# SCH_rfid2final_2025-07-08_1.net
KiCad netlist of a schematic drawn in EasyEDA
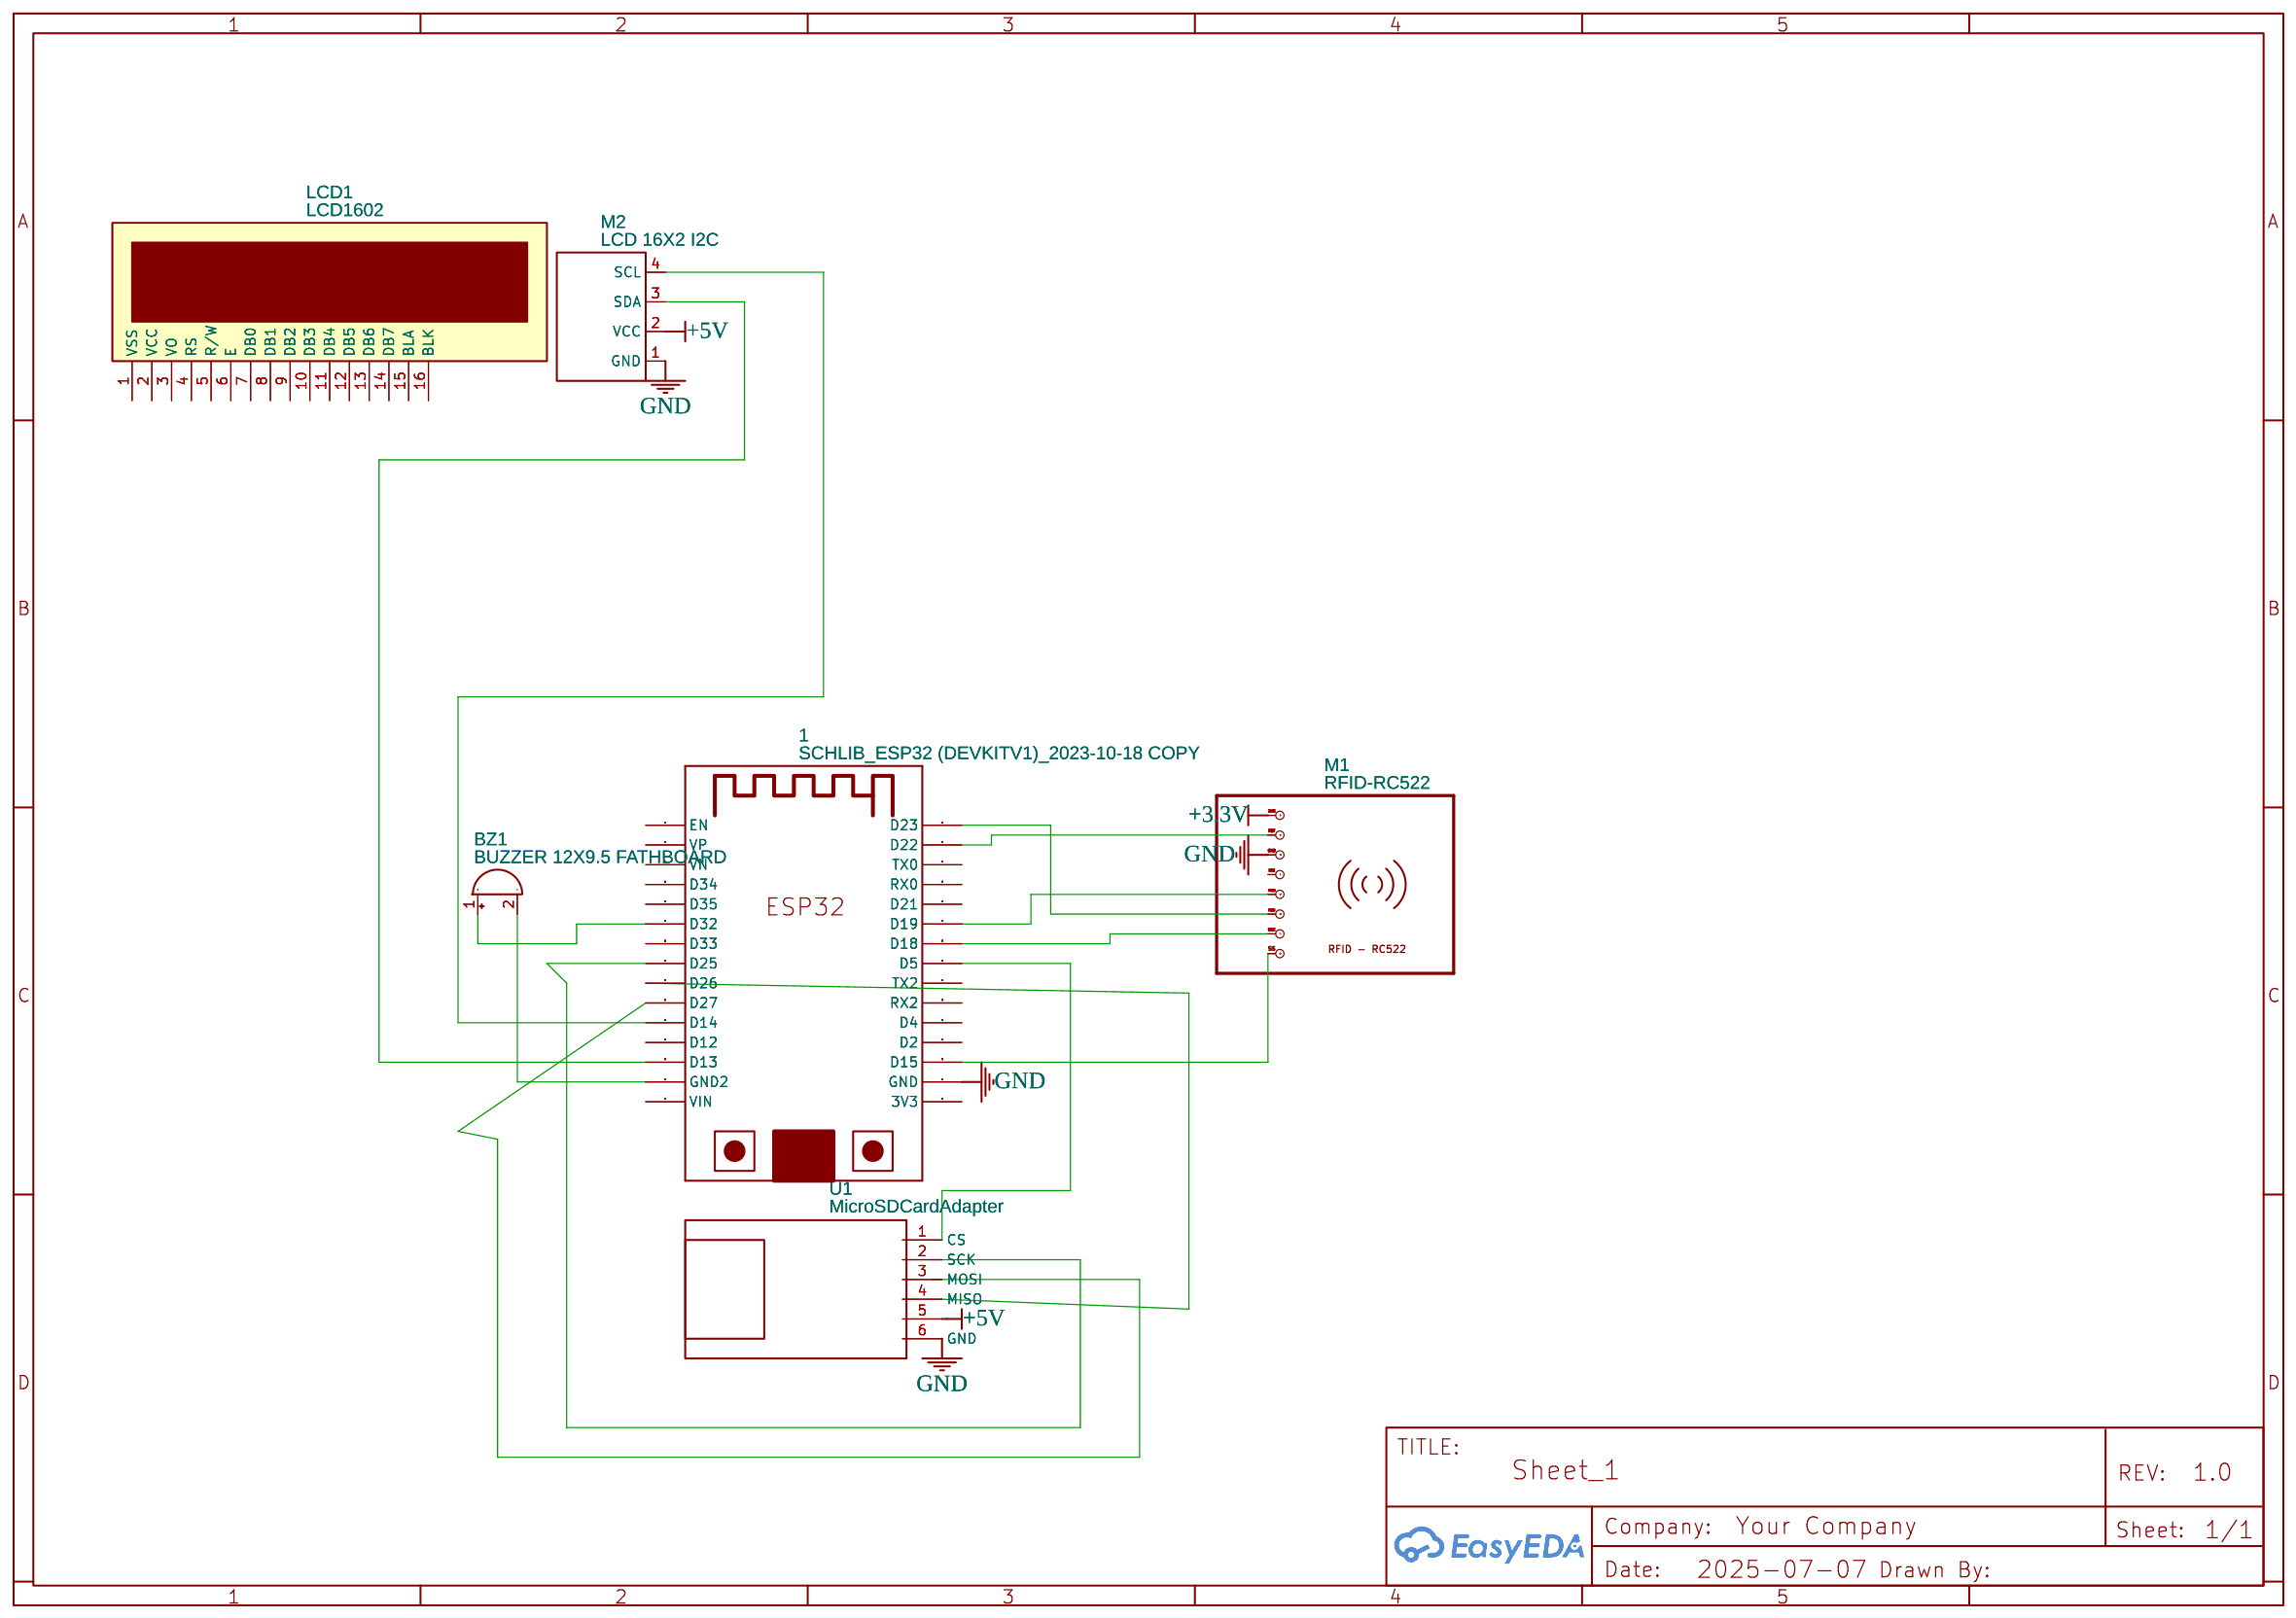
[diagram p0: schematic sheet]

(export (version "E")
  (design (tool "Eeschema 10.0.6"))
  (components
    (comp (ref "1")
      (value "SCHLIB_ESP32 (DEVKITV1)_2023-10-18 COPY")
      (libsource (lib "") (part "ESP32-DEVKIT-V1-30PIN"))
    )
    (comp (ref "BZ1") (value "BUZZER 12X9.5 FATHBOARD") (libsource (lib "") (part "BUZZER 12X9.5 FATHBOARD")))
    (comp (ref "LCD1")
      (value "LCD1602")
      (fields
        (field (name "Manufacturer Part") "LCM1602K-NSW-BBW")
        (field (name "Manufacturer") "LONTECH(厦门龙特)")
      )
      (libsource (lib "") (part "LCD1602"))
    )
    (comp (ref "M1") (value "RFID-RC522") (libsource (lib "") (part "RFID-RC522")))
    (comp (ref "M2") (value "LCD 16X2 I2C") (libsource (lib "") (part "LCD 16X2 I2C")))
    (comp (ref "U1") (value "MicroSDCardAdapter") (libsource (lib "") (part "MicroSDCardAdapter")))
  )
  (nets
    (net (code "1") (name "+3.3V") (class "Default")
      (node (ref "M1") (pin "3V3") (pinfunction "1_3V3") (pintype "bidirectional"))
    )
    (net (code "2") (name "+5V") (class "Default")
      (node (ref "M2") (pin "2") (pinfunction "VCC_2") (pintype "unspecified"))
    )
    (net (code "3") (name "GND") (class "Default")
      (node (ref "1") (pin "GND") (pinfunction "GND_GND") (pintype "unspecified"))
      (node (ref "M1") (pin "GND") (pinfunction "3_GND") (pintype "bidirectional"))
      (node (ref "M2") (pin "1") (pinfunction "GND_1") (pintype "unspecified"))
    )
    (net (code "4") (name "Net-(BZ1-+)") (class "Default")
      (node (ref "1") (pin "D32") (pinfunction "D32_D32") (pintype "unspecified"))
      (node (ref "BZ1") (pin "1") (pinfunction "+_1") (pintype "unspecified"))
    )
    (net (code "5") (name "Net-(BZ1--)") (class "Default")
      (node (ref "1") (pin "GND2") (pinfunction "GND2_GND2") (pintype "unspecified"))
      (node (ref "BZ1") (pin "2") (pinfunction "-_2") (pintype "unspecified"))
    )
    (net (code "6") (name "Net-(M1-2)") (class "Default")
      (node (ref "1") (pin "D22") (pinfunction "D22_D22") (pintype "unspecified"))
      (node (ref "M1") (pin "RST") (pinfunction "2_RST") (pintype "bidirectional"))
    )
    (net (code "7") (name "Net-(M1-5)") (class "Default")
      (node (ref "1") (pin "D19") (pinfunction "D19_D19") (pintype "unspecified"))
      (node (ref "M1") (pin "MISO") (pinfunction "5_MISO") (pintype "bidirectional"))
    )
    (net (code "8") (name "Net-(M1-6)") (class "Default")
      (node (ref "1") (pin "D23") (pinfunction "D23_D23") (pintype "unspecified"))
      (node (ref "M1") (pin "MOSI") (pinfunction "6_MOSI") (pintype "bidirectional"))
    )
    (net (code "9") (name "Net-(M1-7)") (class "Default")
      (node (ref "1") (pin "D18") (pinfunction "D18_D18") (pintype "unspecified"))
      (node (ref "M1") (pin "SCK") (pinfunction "7_SCK") (pintype "bidirectional"))
    )
    (net (code "10") (name "Net-(M1-8)") (class "Default")
      (node (ref "1") (pin "D15") (pinfunction "D15_D15") (pintype "unspecified"))
      (node (ref "M1") (pin "SS") (pinfunction "8_SS") (pintype "bidirectional"))
    )
    (net (code "11") (name "Net-(M2-SCL)") (class "Default")
      (node (ref "1") (pin "D14") (pinfunction "D14_D14") (pintype "unspecified"))
      (node (ref "M2") (pin "4") (pinfunction "SCL_4") (pintype "unspecified"))
    )
    (net (code "12") (name "Net-(M2-SDA)") (class "Default")
      (node (ref "1") (pin "D13") (pinfunction "D13_D13") (pintype "unspecified"))
      (node (ref "M2") (pin "3") (pinfunction "SDA_3") (pintype "unspecified"))
    )
    (net (code "13") (name "unconnected-(1-Pad3V3)") (class "Default")
      (node (ref "1") (pin "3V3") (pinfunction "3V3_3V3") (pintype "unspecified"))
    )
    (net (code "14") (name "unconnected-(1-PadD2)") (class "Default")
      (node (ref "1") (pin "D2") (pinfunction "D2_D2") (pintype "unspecified"))
    )
    (net (code "15") (name "unconnected-(1-PadD4)") (class "Default")
      (node (ref "1") (pin "D4") (pinfunction "D4_D4") (pintype "unspecified"))
    )
    (net (code "16") (name "unconnected-(1-PadD5)") (class "Default")
      (node (ref "1") (pin "D5") (pinfunction "D5_D5") (pintype "unspecified"))
    )
    (net (code "17") (name "unconnected-(1-PadD12)") (class "Default")
      (node (ref "1") (pin "D12") (pinfunction "D12_D12") (pintype "unspecified"))
    )
    (net (code "18") (name "unconnected-(1-PadD21)") (class "Default")
      (node (ref "1") (pin "D21") (pinfunction "D21_D21") (pintype "unspecified"))
    )
    (net (code "19") (name "unconnected-(1-PadD25)") (class "Default")
      (node (ref "1") (pin "D25") (pinfunction "D25_D25") (pintype "unspecified"))
    )
    (net (code "20") (name "unconnected-(1-PadD26)") (class "Default")
      (node (ref "1") (pin "D26") (pinfunction "D26_D26") (pintype "unspecified"))
    )
    (net (code "21") (name "unconnected-(1-PadD27)") (class "Default")
      (node (ref "1") (pin "D27") (pinfunction "D27_D27") (pintype "unspecified"))
    )
    (net (code "22") (name "unconnected-(1-PadD33)") (class "Default")
      (node (ref "1") (pin "D33") (pinfunction "D33_D33") (pintype "unspecified"))
    )
    (net (code "23") (name "unconnected-(1-PadD34)") (class "Default")
      (node (ref "1") (pin "D34") (pinfunction "D34_D34") (pintype "unspecified"))
    )
    (net (code "24") (name "unconnected-(1-PadD35)") (class "Default")
      (node (ref "1") (pin "D35") (pinfunction "D35_D35") (pintype "unspecified"))
    )
    (net (code "25") (name "unconnected-(1-PadEN)") (class "Default")
      (node (ref "1") (pin "EN") (pinfunction "EN_EN") (pintype "unspecified"))
    )
    (net (code "26") (name "unconnected-(1-PadRX0)") (class "Default")
      (node (ref "1") (pin "RX0") (pinfunction "RX0_RX0") (pintype "unspecified"))
    )
    (net (code "27") (name "unconnected-(1-PadRX2)") (class "Default")
      (node (ref "1") (pin "RX2") (pinfunction "RX2_RX2") (pintype "unspecified"))
    )
    (net (code "28") (name "unconnected-(1-PadTX0)") (class "Default")
      (node (ref "1") (pin "TX0") (pinfunction "TX0_TX0") (pintype "unspecified"))
    )
    (net (code "29") (name "unconnected-(1-PadTX2)") (class "Default")
      (node (ref "1") (pin "TX2") (pinfunction "TX2_TX2") (pintype "unspecified"))
    )
    (net (code "30") (name "unconnected-(1-PadVIN)") (class "Default")
      (node (ref "1") (pin "VIN") (pinfunction "VIN_VIN") (pintype "unspecified"))
    )
    (net (code "31") (name "unconnected-(1-PadVN)") (class "Default")
      (node (ref "1") (pin "VN") (pinfunction "VN_VN") (pintype "unspecified"))
    )
    (net (code "32") (name "unconnected-(1-PadVP)") (class "Default")
      (node (ref "1") (pin "VP") (pinfunction "VP_VP") (pintype "unspecified"))
    )
    (net (code "33") (name "unconnected-(LCD1-BLA-Pad15)") (class "Default")
      (node (ref "LCD1") (pin "15") (pinfunction "BLA_15") (pintype "unspecified"))
    )
    (net (code "34") (name "unconnected-(LCD1-BLK-Pad16)") (class "Default")
      (node (ref "LCD1") (pin "16") (pinfunction "BLK_16") (pintype "unspecified"))
    )
    (net (code "35") (name "unconnected-(LCD1-DB0-Pad7)") (class "Default")
      (node (ref "LCD1") (pin "7") (pinfunction "DB0_7") (pintype "unspecified"))
    )
    (net (code "36") (name "unconnected-(LCD1-DB1-Pad8)") (class "Default")
      (node (ref "LCD1") (pin "8") (pinfunction "DB1_8") (pintype "unspecified"))
    )
    (net (code "37") (name "unconnected-(LCD1-DB2-Pad9)") (class "Default")
      (node (ref "LCD1") (pin "9") (pinfunction "DB2_9") (pintype "unspecified"))
    )
    (net (code "38") (name "unconnected-(LCD1-DB3-Pad10)") (class "Default")
      (node (ref "LCD1") (pin "10") (pinfunction "DB3_10") (pintype "unspecified"))
    )
    (net (code "39") (name "unconnected-(LCD1-DB4-Pad11)") (class "Default")
      (node (ref "LCD1") (pin "11") (pinfunction "DB4_11") (pintype "unspecified"))
    )
    (net (code "40") (name "unconnected-(LCD1-DB5-Pad12)") (class "Default")
      (node (ref "LCD1") (pin "12") (pinfunction "DB5_12") (pintype "unspecified"))
    )
    (net (code "41") (name "unconnected-(LCD1-DB6-Pad13)") (class "Default")
      (node (ref "LCD1") (pin "13") (pinfunction "DB6_13") (pintype "unspecified"))
    )
    (net (code "42") (name "unconnected-(LCD1-DB7-Pad14)") (class "Default")
      (node (ref "LCD1") (pin "14") (pinfunction "DB7_14") (pintype "unspecified"))
    )
    (net (code "43") (name "unconnected-(LCD1-E-Pad6)") (class "Default")
      (node (ref "LCD1") (pin "6") (pinfunction "E_6") (pintype "unspecified"))
    )
    (net (code "44") (name "unconnected-(LCD1-RS-Pad4)") (class "Default")
      (node (ref "LCD1") (pin "4") (pinfunction "RS_4") (pintype "unspecified"))
    )
    (net (code "45") (name "unconnected-(LCD1-R{slash}W-Pad5)") (class "Default")
      (node (ref "LCD1") (pin "5") (pinfunction "R/W_5") (pintype "unspecified"))
    )
    (net (code "46") (name "unconnected-(LCD1-VCC-Pad2)") (class "Default")
      (node (ref "LCD1") (pin "2") (pinfunction "VCC_2") (pintype "unspecified"))
    )
    (net (code "47") (name "unconnected-(LCD1-VO-Pad3)") (class "Default")
      (node (ref "LCD1") (pin "3") (pinfunction "VO_3") (pintype "unspecified"))
    )
    (net (code "48") (name "unconnected-(LCD1-VSS-Pad1)") (class "Default")
      (node (ref "LCD1") (pin "1") (pinfunction "VSS_1") (pintype "unspecified"))
    )
    (net (code "49") (name "unconnected-(M1-4-PadIRQ)") (class "Default")
      (node (ref "M1") (pin "IRQ") (pinfunction "4_IRQ") (pintype "bidirectional"))
    )
    (net (code "50") (name "unconnected-(U1-CS-Pad1)") (class "Default")
      (node (ref "U1") (pin "1") (pinfunction "CS_1") (pintype "unspecified"))
    )
    (net (code "51") (name "unconnected-(U1-GND-Pad6)") (class "Default")
      (node (ref "U1") (pin "6") (pinfunction "GND_6") (pintype "unspecified"))
    )
    (net (code "52") (name "unconnected-(U1-MISO-Pad4)") (class "Default")
      (node (ref "U1") (pin "4") (pinfunction "MISO_4") (pintype "unspecified"))
    )
    (net (code "53") (name "unconnected-(U1-MOSI-Pad3)") (class "Default")
      (node (ref "U1") (pin "3") (pinfunction "MOSI_3") (pintype "unspecified"))
    )
    (net (code "54") (name "unconnected-(U1-SCK-Pad2)") (class "Default")
      (node (ref "U1") (pin "2") (pinfunction "SCK_2") (pintype "unspecified"))
    )
    (net (code "55") (name "unconnected-(U1-VCC-Pad5)") (class "Default")
      (node (ref "U1") (pin "5") (pinfunction "VCC_5") (pintype "unspecified"))
    )
  )
)
